# LoadCell-Board.net
KiCad netlist of a schematic drawn in EAGLE
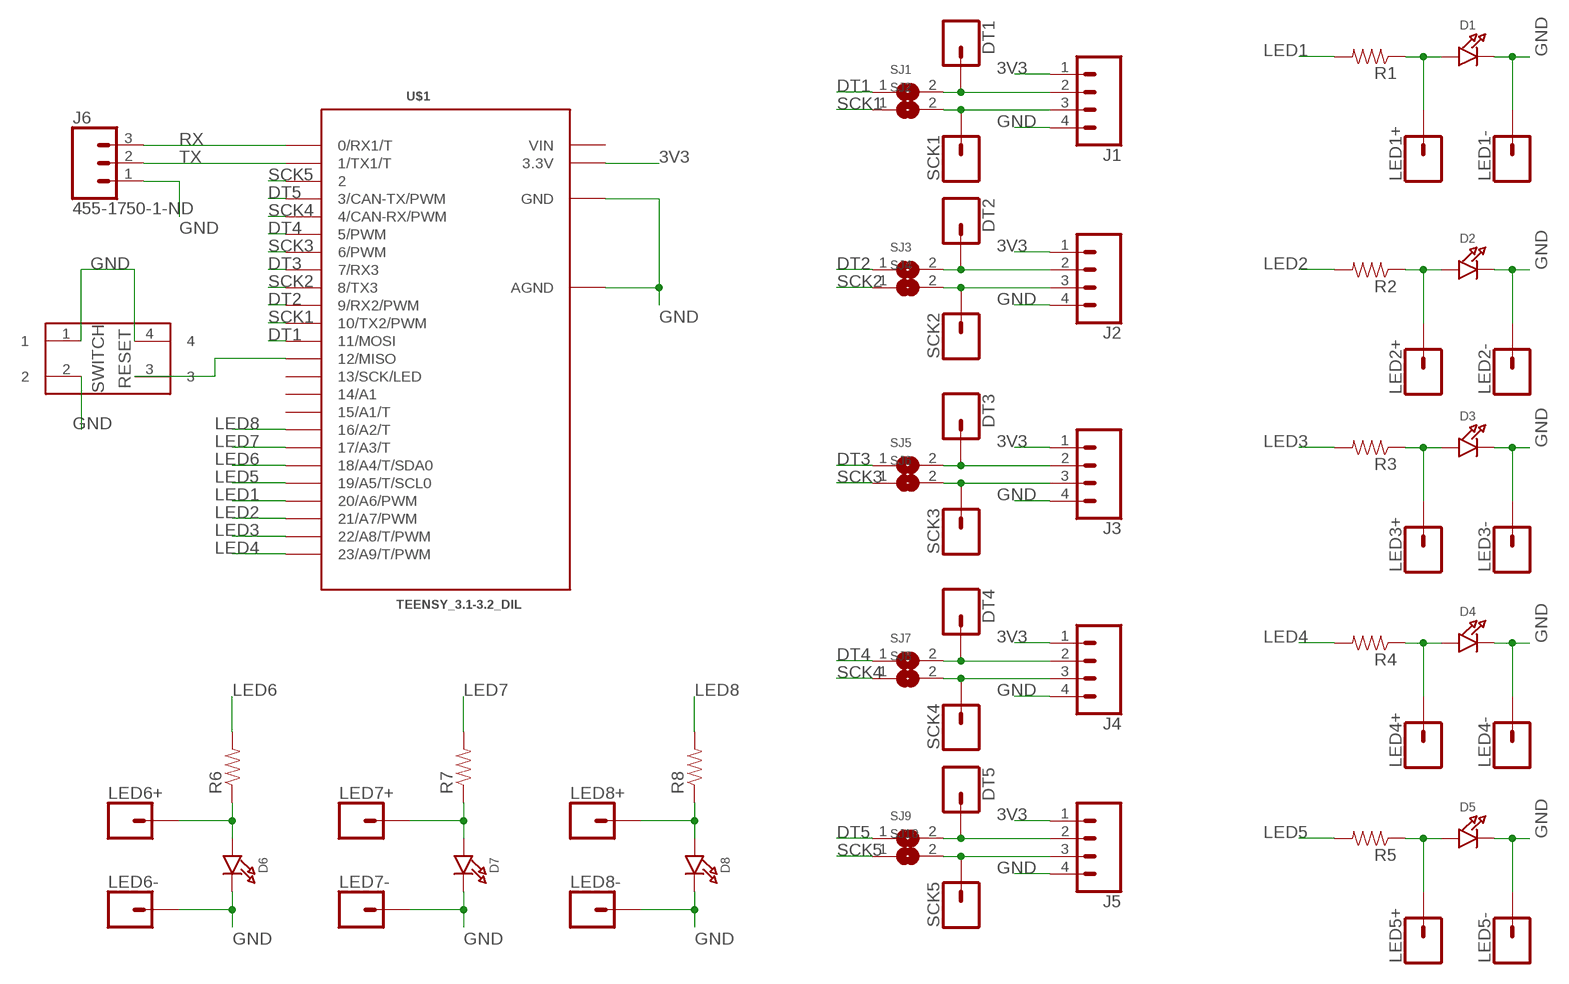
[diagram p0: schematic, sheet 1]

(export (version "E")
  (design (tool "Eeschema 10.0.6"))
  (components
    (comp (ref "D1")
      (value "MICROBUILDER_LED0603")
      (footprint "eagle-import:MICROBUILDER_CHIPLED_0603")
      (libsource (lib "eagle-import") (part "MICROBUILDER_LED0603"))
    )
    (comp (ref "D2")
      (value "MICROBUILDER_LED0603")
      (footprint "eagle-import:MICROBUILDER_CHIPLED_0603")
      (libsource (lib "eagle-import") (part "MICROBUILDER_LED0603"))
    )
    (comp (ref "D3")
      (value "MICROBUILDER_LED0603")
      (footprint "eagle-import:MICROBUILDER_CHIPLED_0603")
      (libsource (lib "eagle-import") (part "MICROBUILDER_LED0603"))
    )
    (comp (ref "D4")
      (value "MICROBUILDER_LED0603")
      (footprint "eagle-import:MICROBUILDER_CHIPLED_0603")
      (libsource (lib "eagle-import") (part "MICROBUILDER_LED0603"))
    )
    (comp (ref "D5")
      (value "MICROBUILDER_LED0603")
      (footprint "eagle-import:MICROBUILDER_CHIPLED_0603")
      (libsource (lib "eagle-import") (part "MICROBUILDER_LED0603"))
    )
    (comp (ref "D6")
      (value "MICROBUILDER_LED0603")
      (footprint "eagle-import:MICROBUILDER_CHIPLED_0603")
      (libsource (lib "eagle-import") (part "MICROBUILDER_LED0603"))
    )
    (comp (ref "D7")
      (value "MICROBUILDER_LED0603")
      (footprint "eagle-import:MICROBUILDER_CHIPLED_0603")
      (libsource (lib "eagle-import") (part "MICROBUILDER_LED0603"))
    )
    (comp (ref "D8")
      (value "MICROBUILDER_LED0603")
      (footprint "eagle-import:MICROBUILDER_CHIPLED_0603")
      (libsource (lib "eagle-import") (part "MICROBUILDER_LED0603"))
    )
    (comp (ref "DT1")
      (value "CONN_01")
      (footprint "eagle-import:1X01")
      (libsource (lib "eagle-import") (part "CONN_01"))
    )
    (comp (ref "DT2")
      (value "CONN_01")
      (footprint "eagle-import:1X01")
      (libsource (lib "eagle-import") (part "CONN_01"))
    )
    (comp (ref "DT3")
      (value "CONN_01")
      (footprint "eagle-import:1X01")
      (libsource (lib "eagle-import") (part "CONN_01"))
    )
    (comp (ref "DT4")
      (value "CONN_01")
      (footprint "eagle-import:1X01")
      (libsource (lib "eagle-import") (part "CONN_01"))
    )
    (comp (ref "DT5")
      (value "CONN_01")
      (footprint "eagle-import:1X01")
      (libsource (lib "eagle-import") (part "CONN_01"))
    )
    (comp (ref "J1")
      (value "CONN_041X04_NO_SILK")
      (footprint "eagle-import:1X04_NO_SILK")
      (libsource (lib "eagle-import") (part "CONN_041X04_NO_SILK"))
    )
    (comp (ref "J2")
      (value "CONN_041X04_NO_SILK")
      (footprint "eagle-import:1X04_NO_SILK")
      (libsource (lib "eagle-import") (part "CONN_041X04_NO_SILK"))
    )
    (comp (ref "J3")
      (value "CONN_041X04_NO_SILK")
      (footprint "eagle-import:1X04_NO_SILK")
      (libsource (lib "eagle-import") (part "CONN_041X04_NO_SILK"))
    )
    (comp (ref "J4")
      (value "CONN_041X04_NO_SILK")
      (footprint "eagle-import:1X04_NO_SILK")
      (libsource (lib "eagle-import") (part "CONN_041X04_NO_SILK"))
    )
    (comp (ref "J5")
      (value "CONN_041X04_NO_SILK")
      (footprint "eagle-import:1X04_NO_SILK")
      (libsource (lib "eagle-import") (part "CONN_041X04_NO_SILK"))
    )
    (comp (ref "J6")
      (value "455-1750-1-ND")
      (footprint "eagle-import:1X03")
      (libsource (lib "eagle-import") (part "CONN_03"))
    )
    (comp (ref "LED1+")
      (value "CONN_01PTH_NO_SILK_YES_STOP")
      (footprint "eagle-import:1X01_NO_SILK")
      (libsource (lib "eagle-import") (part "CONN_01PTH_NO_SILK_YES_STOP"))
    )
    (comp (ref "LED1-")
      (value "CONN_01PTH_NO_SILK_YES_STOP")
      (footprint "eagle-import:1X01_NO_SILK")
      (libsource (lib "eagle-import") (part "CONN_01PTH_NO_SILK_YES_STOP"))
    )
    (comp (ref "LED2+")
      (value "CONN_01PTH_NO_SILK_YES_STOP")
      (footprint "eagle-import:1X01_NO_SILK")
      (libsource (lib "eagle-import") (part "CONN_01PTH_NO_SILK_YES_STOP"))
    )
    (comp (ref "LED2-")
      (value "CONN_01PTH_NO_SILK_YES_STOP")
      (footprint "eagle-import:1X01_NO_SILK")
      (libsource (lib "eagle-import") (part "CONN_01PTH_NO_SILK_YES_STOP"))
    )
    (comp (ref "LED3+")
      (value "CONN_01PTH_NO_SILK_YES_STOP")
      (footprint "eagle-import:1X01_NO_SILK")
      (libsource (lib "eagle-import") (part "CONN_01PTH_NO_SILK_YES_STOP"))
    )
    (comp (ref "LED3-")
      (value "CONN_01PTH_NO_SILK_YES_STOP")
      (footprint "eagle-import:1X01_NO_SILK")
      (libsource (lib "eagle-import") (part "CONN_01PTH_NO_SILK_YES_STOP"))
    )
    (comp (ref "LED4+")
      (value "CONN_01PTH_NO_SILK_YES_STOP")
      (footprint "eagle-import:1X01_NO_SILK")
      (libsource (lib "eagle-import") (part "CONN_01PTH_NO_SILK_YES_STOP"))
    )
    (comp (ref "LED4-")
      (value "CONN_01PTH_NO_SILK_YES_STOP")
      (footprint "eagle-import:1X01_NO_SILK")
      (libsource (lib "eagle-import") (part "CONN_01PTH_NO_SILK_YES_STOP"))
    )
    (comp (ref "LED5+")
      (value "CONN_01PTH_NO_SILK_YES_STOP")
      (footprint "eagle-import:1X01_NO_SILK")
      (libsource (lib "eagle-import") (part "CONN_01PTH_NO_SILK_YES_STOP"))
    )
    (comp (ref "LED5-")
      (value "CONN_01PTH_NO_SILK_YES_STOP")
      (footprint "eagle-import:1X01_NO_SILK")
      (libsource (lib "eagle-import") (part "CONN_01PTH_NO_SILK_YES_STOP"))
    )
    (comp (ref "LED6+")
      (value "CONN_01PTH_NO_SILK_YES_STOP")
      (footprint "eagle-import:1X01_NO_SILK")
      (libsource (lib "eagle-import") (part "CONN_01PTH_NO_SILK_YES_STOP"))
    )
    (comp (ref "LED6-")
      (value "CONN_01PTH_NO_SILK_YES_STOP")
      (footprint "eagle-import:1X01_NO_SILK")
      (libsource (lib "eagle-import") (part "CONN_01PTH_NO_SILK_YES_STOP"))
    )
    (comp (ref "LED7+")
      (value "CONN_01PTH_NO_SILK_YES_STOP")
      (footprint "eagle-import:1X01_NO_SILK")
      (libsource (lib "eagle-import") (part "CONN_01PTH_NO_SILK_YES_STOP"))
    )
    (comp (ref "LED7-")
      (value "CONN_01PTH_NO_SILK_YES_STOP")
      (footprint "eagle-import:1X01_NO_SILK")
      (libsource (lib "eagle-import") (part "CONN_01PTH_NO_SILK_YES_STOP"))
    )
    (comp (ref "LED8+")
      (value "CONN_01PTH_NO_SILK_YES_STOP")
      (footprint "eagle-import:1X01_NO_SILK")
      (libsource (lib "eagle-import") (part "CONN_01PTH_NO_SILK_YES_STOP"))
    )
    (comp (ref "LED8-")
      (value "CONN_01PTH_NO_SILK_YES_STOP")
      (footprint "eagle-import:1X01_NO_SILK")
      (libsource (lib "eagle-import") (part "CONN_01PTH_NO_SILK_YES_STOP"))
    )
    (comp (ref "R1")
      (value "CONTROLBOARD_V1.0_SPARKFUN_RESISTOR0603-RES")
      (footprint "eagle-import:CONTROLBOARD_V1.0_SPARKFUN_0603-RES")
      (libsource (lib "eagle-import") (part "CONTROLBOARD_V1.0_SPARKFUN_RESISTOR0603-RES"))
    )
    (comp (ref "R2")
      (value "CONTROLBOARD_V1.0_SPARKFUN_RESISTOR0603-RES")
      (footprint "eagle-import:CONTROLBOARD_V1.0_SPARKFUN_0603-RES")
      (libsource (lib "eagle-import") (part "CONTROLBOARD_V1.0_SPARKFUN_RESISTOR0603-RES"))
    )
    (comp (ref "R3")
      (value "CONTROLBOARD_V1.0_SPARKFUN_RESISTOR0603-RES")
      (footprint "eagle-import:CONTROLBOARD_V1.0_SPARKFUN_0603-RES")
      (libsource (lib "eagle-import") (part "CONTROLBOARD_V1.0_SPARKFUN_RESISTOR0603-RES"))
    )
    (comp (ref "R4")
      (value "CONTROLBOARD_V1.0_SPARKFUN_RESISTOR0603-RES")
      (footprint "eagle-import:CONTROLBOARD_V1.0_SPARKFUN_0603-RES")
      (libsource (lib "eagle-import") (part "CONTROLBOARD_V1.0_SPARKFUN_RESISTOR0603-RES"))
    )
    (comp (ref "R5")
      (value "CONTROLBOARD_V1.0_SPARKFUN_RESISTOR0603-RES")
      (footprint "eagle-import:CONTROLBOARD_V1.0_SPARKFUN_0603-RES")
      (libsource (lib "eagle-import") (part "CONTROLBOARD_V1.0_SPARKFUN_RESISTOR0603-RES"))
    )
    (comp (ref "R6")
      (value "CONTROLBOARD_V1.0_SPARKFUN_RESISTOR0603-RES")
      (footprint "eagle-import:CONTROLBOARD_V1.0_SPARKFUN_0603-RES")
      (libsource (lib "eagle-import") (part "CONTROLBOARD_V1.0_SPARKFUN_RESISTOR0603-RES"))
    )
    (comp (ref "R7")
      (value "CONTROLBOARD_V1.0_SPARKFUN_RESISTOR0603-RES")
      (footprint "eagle-import:CONTROLBOARD_V1.0_SPARKFUN_0603-RES")
      (libsource (lib "eagle-import") (part "CONTROLBOARD_V1.0_SPARKFUN_RESISTOR0603-RES"))
    )
    (comp (ref "R8")
      (value "CONTROLBOARD_V1.0_SPARKFUN_RESISTOR0603-RES")
      (footprint "eagle-import:CONTROLBOARD_V1.0_SPARKFUN_0603-RES")
      (libsource (lib "eagle-import") (part "CONTROLBOARD_V1.0_SPARKFUN_RESISTOR0603-RES"))
    )
    (comp (ref "RESET")
      (value "SWITCH")
      (footprint "eagle-import:431256038716")
      (libsource (lib "eagle-import") (part "431256038716"))
    )
    (comp (ref "SCK1")
      (value "CONN_01")
      (footprint "eagle-import:1X01")
      (libsource (lib "eagle-import") (part "CONN_01"))
    )
    (comp (ref "SCK2")
      (value "CONN_01")
      (footprint "eagle-import:1X01")
      (libsource (lib "eagle-import") (part "CONN_01"))
    )
    (comp (ref "SCK3")
      (value "CONN_01")
      (footprint "eagle-import:1X01")
      (libsource (lib "eagle-import") (part "CONN_01"))
    )
    (comp (ref "SCK4")
      (value "CONN_01")
      (footprint "eagle-import:1X01")
      (libsource (lib "eagle-import") (part "CONN_01"))
    )
    (comp (ref "SCK5")
      (value "CONN_01")
      (footprint "eagle-import:1X01")
      (libsource (lib "eagle-import") (part "CONN_01"))
    )
    (comp (ref "SJ1")
      (value "MICROBUILDER_SOLDERJUMPERREFLOW_NOPASTE")
      (footprint "eagle-import:MICROBUILDER_SOLDERJUMPER_REFLOW_NOPASTE")
      (libsource (lib "eagle-import") (part "MICROBUILDER_SOLDERJUMPERREFLOW_NOPASTE"))
    )
    (comp (ref "SJ2")
      (value "MICROBUILDER_SOLDERJUMPERREFLOW_NOPASTE")
      (footprint "eagle-import:MICROBUILDER_SOLDERJUMPER_REFLOW_NOPASTE")
      (libsource (lib "eagle-import") (part "MICROBUILDER_SOLDERJUMPERREFLOW_NOPASTE"))
    )
    (comp (ref "SJ3")
      (value "MICROBUILDER_SOLDERJUMPERREFLOW_NOPASTE")
      (footprint "eagle-import:MICROBUILDER_SOLDERJUMPER_REFLOW_NOPASTE")
      (libsource (lib "eagle-import") (part "MICROBUILDER_SOLDERJUMPERREFLOW_NOPASTE"))
    )
    (comp (ref "SJ4")
      (value "MICROBUILDER_SOLDERJUMPERREFLOW_NOPASTE")
      (footprint "eagle-import:MICROBUILDER_SOLDERJUMPER_REFLOW_NOPASTE")
      (libsource (lib "eagle-import") (part "MICROBUILDER_SOLDERJUMPERREFLOW_NOPASTE"))
    )
    (comp (ref "SJ5")
      (value "MICROBUILDER_SOLDERJUMPERREFLOW_NOPASTE")
      (footprint "eagle-import:MICROBUILDER_SOLDERJUMPER_REFLOW_NOPASTE")
      (libsource (lib "eagle-import") (part "MICROBUILDER_SOLDERJUMPERREFLOW_NOPASTE"))
    )
    (comp (ref "SJ6")
      (value "MICROBUILDER_SOLDERJUMPERREFLOW_NOPASTE")
      (footprint "eagle-import:MICROBUILDER_SOLDERJUMPER_REFLOW_NOPASTE")
      (libsource (lib "eagle-import") (part "MICROBUILDER_SOLDERJUMPERREFLOW_NOPASTE"))
    )
    (comp (ref "SJ7")
      (value "MICROBUILDER_SOLDERJUMPERREFLOW_NOPASTE")
      (footprint "eagle-import:MICROBUILDER_SOLDERJUMPER_REFLOW_NOPASTE")
      (libsource (lib "eagle-import") (part "MICROBUILDER_SOLDERJUMPERREFLOW_NOPASTE"))
    )
    (comp (ref "SJ8")
      (value "MICROBUILDER_SOLDERJUMPERREFLOW_NOPASTE")
      (footprint "eagle-import:MICROBUILDER_SOLDERJUMPER_REFLOW_NOPASTE")
      (libsource (lib "eagle-import") (part "MICROBUILDER_SOLDERJUMPERREFLOW_NOPASTE"))
    )
    (comp (ref "SJ9")
      (value "MICROBUILDER_SOLDERJUMPERREFLOW_NOPASTE")
      (footprint "eagle-import:MICROBUILDER_SOLDERJUMPER_REFLOW_NOPASTE")
      (libsource (lib "eagle-import") (part "MICROBUILDER_SOLDERJUMPERREFLOW_NOPASTE"))
    )
    (comp (ref "SJ10")
      (value "MICROBUILDER_SOLDERJUMPERREFLOW_NOPASTE")
      (footprint "eagle-import:MICROBUILDER_SOLDERJUMPER_REFLOW_NOPASTE")
      (libsource (lib "eagle-import") (part "MICROBUILDER_SOLDERJUMPERREFLOW_NOPASTE"))
    )
    (comp (ref "U$1")
      (value "TEENSY_3.1-3.2_DIL")
      (footprint "eagle-import:TEENSY_3.0-3.2&LC_DIL")
      (libsource (lib "eagle-import") (part "TEENSY_3.1-3.2_DIL"))
    )
  )
  (nets
    (net (code "1") (name "/3V3") (class "Default")
      (node (ref "J1") (pin "1") (pinfunction "1_1") (pintype "passive"))
      (node (ref "J2") (pin "1") (pinfunction "1_1") (pintype "passive"))
      (node (ref "J3") (pin "1") (pinfunction "1_1") (pintype "passive"))
      (node (ref "J4") (pin "1") (pinfunction "1_1") (pintype "passive"))
      (node (ref "J5") (pin "1") (pinfunction "1_1") (pintype "passive"))
      (node (ref "U$1") (pin "3.3V") (pinfunction "3.3V_3.3V") (pintype "power_in"))
    )
    (net (code "2") (name "/DT1") (class "Default")
      (node (ref "SJ1") (pin "1") (pinfunction "1_1") (pintype "passive"))
      (node (ref "U$1") (pin "11") (pinfunction "11/MOSI_11") (pintype "bidirectional"))
    )
    (net (code "3") (name "/DT2") (class "Default")
      (node (ref "SJ3") (pin "1") (pinfunction "1_1") (pintype "passive"))
      (node (ref "U$1") (pin "9") (pinfunction "9/RX2/PWM_9") (pintype "bidirectional"))
    )
    (net (code "4") (name "/DT3") (class "Default")
      (node (ref "SJ5") (pin "1") (pinfunction "1_1") (pintype "passive"))
      (node (ref "U$1") (pin "7") (pinfunction "7/RX3_7") (pintype "bidirectional"))
    )
    (net (code "5") (name "/DT4") (class "Default")
      (node (ref "SJ7") (pin "1") (pinfunction "1_1") (pintype "passive"))
      (node (ref "U$1") (pin "5") (pinfunction "5/PWM_5") (pintype "bidirectional"))
    )
    (net (code "6") (name "/DT5") (class "Default")
      (node (ref "SJ9") (pin "1") (pinfunction "1_1") (pintype "passive"))
      (node (ref "U$1") (pin "3") (pinfunction "3/CAN-TX/PWM_3") (pintype "bidirectional"))
    )
    (net (code "7") (name "/GND") (class "Default")
      (node (ref "D1") (pin "C") (pinfunction "C_C") (pintype "passive"))
      (node (ref "D2") (pin "C") (pinfunction "C_C") (pintype "passive"))
      (node (ref "D3") (pin "C") (pinfunction "C_C") (pintype "passive"))
      (node (ref "D4") (pin "C") (pinfunction "C_C") (pintype "passive"))
      (node (ref "D5") (pin "C") (pinfunction "C_C") (pintype "passive"))
      (node (ref "D6") (pin "C") (pinfunction "C_C") (pintype "passive"))
      (node (ref "D7") (pin "C") (pinfunction "C_C") (pintype "passive"))
      (node (ref "D8") (pin "C") (pinfunction "C_C") (pintype "passive"))
      (node (ref "J1") (pin "4") (pinfunction "4_4") (pintype "passive"))
      (node (ref "J2") (pin "4") (pinfunction "4_4") (pintype "passive"))
      (node (ref "J3") (pin "4") (pinfunction "4_4") (pintype "passive"))
      (node (ref "J4") (pin "4") (pinfunction "4_4") (pintype "passive"))
      (node (ref "J5") (pin "4") (pinfunction "4_4") (pintype "passive"))
      (node (ref "J6") (pin "1") (pinfunction "1_1") (pintype "passive"))
      (node (ref "LED1-") (pin "1") (pinfunction "1_1") (pintype "passive"))
      (node (ref "LED2-") (pin "1") (pinfunction "1_1") (pintype "passive"))
      (node (ref "LED3-") (pin "1") (pinfunction "1_1") (pintype "passive"))
      (node (ref "LED4-") (pin "1") (pinfunction "1_1") (pintype "passive"))
      (node (ref "LED5-") (pin "1") (pinfunction "1_1") (pintype "passive"))
      (node (ref "LED6-") (pin "1") (pinfunction "1_1") (pintype "passive"))
      (node (ref "LED7-") (pin "1") (pinfunction "1_1") (pintype "passive"))
      (node (ref "LED8-") (pin "1") (pinfunction "1_1") (pintype "passive"))
      (node (ref "RESET") (pin "1") (pinfunction "1_1") (pintype "bidirectional"))
      (node (ref "RESET") (pin "2") (pinfunction "2_2") (pintype "bidirectional"))
      (node (ref "RESET") (pin "4") (pinfunction "4_4") (pintype "bidirectional"))
      (node (ref "U$1") (pin "AGND") (pinfunction "AGND_AGND") (pintype "power_in"))
      (node (ref "U$1") (pin "GND") (pinfunction "GND_GND") (pintype "power_in"))
    )
    (net (code "8") (name "/LED1") (class "Default")
      (node (ref "R1") (pin "2") (pinfunction "2_2") (pintype "passive"))
      (node (ref "U$1") (pin "20/A6") (pinfunction "20/A6/PWM_20/A6") (pintype "bidirectional"))
    )
    (net (code "9") (name "/LED2") (class "Default")
      (node (ref "R2") (pin "2") (pinfunction "2_2") (pintype "passive"))
      (node (ref "U$1") (pin "21/A7") (pinfunction "21/A7/PWM_21/A7") (pintype "bidirectional"))
    )
    (net (code "10") (name "/LED3") (class "Default")
      (node (ref "R3") (pin "2") (pinfunction "2_2") (pintype "passive"))
      (node (ref "U$1") (pin "22/A8") (pinfunction "22/A8/T/PWM_22/A8") (pintype "bidirectional"))
    )
    (net (code "11") (name "/LED4") (class "Default")
      (node (ref "R4") (pin "2") (pinfunction "2_2") (pintype "passive"))
      (node (ref "U$1") (pin "23/A9") (pinfunction "23/A9/T/PWM_23/A9") (pintype "bidirectional"))
    )
    (net (code "12") (name "/LED5") (class "Default")
      (node (ref "R5") (pin "2") (pinfunction "2_2") (pintype "passive"))
      (node (ref "U$1") (pin "19/A5") (pinfunction "19/A5/T/SCL0_19/A5") (pintype "bidirectional"))
    )
    (net (code "13") (name "/LED6") (class "Default")
      (node (ref "R6") (pin "2") (pinfunction "2_2") (pintype "passive"))
      (node (ref "U$1") (pin "18/A4") (pinfunction "18/A4/T/SDA0_18/A4") (pintype "bidirectional"))
    )
    (net (code "14") (name "/LED7") (class "Default")
      (node (ref "R7") (pin "2") (pinfunction "2_2") (pintype "passive"))
      (node (ref "U$1") (pin "17/A3") (pinfunction "17/A3/T_17/A3") (pintype "bidirectional"))
    )
    (net (code "15") (name "/LED8") (class "Default")
      (node (ref "R8") (pin "2") (pinfunction "2_2") (pintype "passive"))
      (node (ref "U$1") (pin "16/A2") (pinfunction "16/A2/T_16/A2") (pintype "bidirectional"))
    )
    (net (code "16") (name "/RX") (class "Default")
      (node (ref "J6") (pin "3") (pinfunction "3_3") (pintype "passive"))
      (node (ref "U$1") (pin "0") (pinfunction "0/RX1/T_0") (pintype "bidirectional"))
    )
    (net (code "17") (name "/SCK1") (class "Default")
      (node (ref "SJ2") (pin "1") (pinfunction "1_1") (pintype "passive"))
      (node (ref "U$1") (pin "10") (pinfunction "10/TX2/PWM_10") (pintype "bidirectional"))
    )
    (net (code "18") (name "/SCK2") (class "Default")
      (node (ref "SJ4") (pin "1") (pinfunction "1_1") (pintype "passive"))
      (node (ref "U$1") (pin "8") (pinfunction "8/TX3_8") (pintype "bidirectional"))
    )
    (net (code "19") (name "/SCK3") (class "Default")
      (node (ref "SJ6") (pin "1") (pinfunction "1_1") (pintype "passive"))
      (node (ref "U$1") (pin "6") (pinfunction "6/PWM_6") (pintype "bidirectional"))
    )
    (net (code "20") (name "/SCK4") (class "Default")
      (node (ref "SJ8") (pin "1") (pinfunction "1_1") (pintype "passive"))
      (node (ref "U$1") (pin "4") (pinfunction "4/CAN-RX/PWM_4") (pintype "bidirectional"))
    )
    (net (code "21") (name "/SCK5") (class "Default")
      (node (ref "SJ10") (pin "1") (pinfunction "1_1") (pintype "passive"))
      (node (ref "U$1") (pin "2") (pinfunction "2_2") (pintype "bidirectional"))
    )
    (net (code "22") (name "/TX") (class "Default")
      (node (ref "J6") (pin "2") (pinfunction "2_2") (pintype "passive"))
      (node (ref "U$1") (pin "1") (pinfunction "1/TX1/T_1") (pintype "bidirectional"))
    )
    (net (code "23") (name "/VIN") (class "Default")
      (node (ref "U$1") (pin "VIN") (pinfunction "VIN_VIN") (pintype "power_in"))
    )
    (net (code "24") (name "Net-(D1-PadA)") (class "Default")
      (node (ref "D1") (pin "A") (pinfunction "A_A") (pintype "passive"))
      (node (ref "LED1+") (pin "1") (pinfunction "1_1") (pintype "passive"))
      (node (ref "R1") (pin "1") (pinfunction "1_1") (pintype "passive"))
    )
    (net (code "25") (name "Net-(D2-PadA)") (class "Default")
      (node (ref "D2") (pin "A") (pinfunction "A_A") (pintype "passive"))
      (node (ref "LED2+") (pin "1") (pinfunction "1_1") (pintype "passive"))
      (node (ref "R2") (pin "1") (pinfunction "1_1") (pintype "passive"))
    )
    (net (code "26") (name "Net-(D3-PadA)") (class "Default")
      (node (ref "D3") (pin "A") (pinfunction "A_A") (pintype "passive"))
      (node (ref "LED3+") (pin "1") (pinfunction "1_1") (pintype "passive"))
      (node (ref "R3") (pin "1") (pinfunction "1_1") (pintype "passive"))
    )
    (net (code "27") (name "Net-(D4-PadA)") (class "Default")
      (node (ref "D4") (pin "A") (pinfunction "A_A") (pintype "passive"))
      (node (ref "LED4+") (pin "1") (pinfunction "1_1") (pintype "passive"))
      (node (ref "R4") (pin "1") (pinfunction "1_1") (pintype "passive"))
    )
    (net (code "28") (name "Net-(D5-PadA)") (class "Default")
      (node (ref "D5") (pin "A") (pinfunction "A_A") (pintype "passive"))
      (node (ref "LED5+") (pin "1") (pinfunction "1_1") (pintype "passive"))
      (node (ref "R5") (pin "1") (pinfunction "1_1") (pintype "passive"))
    )
    (net (code "29") (name "Net-(D6-PadA)") (class "Default")
      (node (ref "D6") (pin "A") (pinfunction "A_A") (pintype "passive"))
      (node (ref "LED6+") (pin "1") (pinfunction "1_1") (pintype "passive"))
      (node (ref "R6") (pin "1") (pinfunction "1_1") (pintype "passive"))
    )
    (net (code "30") (name "Net-(D7-PadA)") (class "Default")
      (node (ref "D7") (pin "A") (pinfunction "A_A") (pintype "passive"))
      (node (ref "LED7+") (pin "1") (pinfunction "1_1") (pintype "passive"))
      (node (ref "R7") (pin "1") (pinfunction "1_1") (pintype "passive"))
    )
    (net (code "31") (name "Net-(D8-PadA)") (class "Default")
      (node (ref "D8") (pin "A") (pinfunction "A_A") (pintype "passive"))
      (node (ref "LED8+") (pin "1") (pinfunction "1_1") (pintype "passive"))
      (node (ref "R8") (pin "1") (pinfunction "1_1") (pintype "passive"))
    )
    (net (code "32") (name "Net-(DT1-Pad1)") (class "Default")
      (node (ref "DT1") (pin "1") (pinfunction "1_1") (pintype "passive"))
      (node (ref "J1") (pin "2") (pinfunction "2_2") (pintype "passive"))
      (node (ref "SJ1") (pin "2") (pinfunction "2_2") (pintype "passive"))
    )
    (net (code "33") (name "Net-(DT2-Pad1)") (class "Default")
      (node (ref "DT2") (pin "1") (pinfunction "1_1") (pintype "passive"))
      (node (ref "J2") (pin "2") (pinfunction "2_2") (pintype "passive"))
      (node (ref "SJ3") (pin "2") (pinfunction "2_2") (pintype "passive"))
    )
    (net (code "34") (name "Net-(DT3-Pad1)") (class "Default")
      (node (ref "DT3") (pin "1") (pinfunction "1_1") (pintype "passive"))
      (node (ref "J3") (pin "2") (pinfunction "2_2") (pintype "passive"))
      (node (ref "SJ5") (pin "2") (pinfunction "2_2") (pintype "passive"))
    )
    (net (code "35") (name "Net-(DT4-Pad1)") (class "Default")
      (node (ref "DT4") (pin "1") (pinfunction "1_1") (pintype "passive"))
      (node (ref "J4") (pin "2") (pinfunction "2_2") (pintype "passive"))
      (node (ref "SJ7") (pin "2") (pinfunction "2_2") (pintype "passive"))
    )
    (net (code "36") (name "Net-(DT5-Pad1)") (class "Default")
      (node (ref "DT5") (pin "1") (pinfunction "1_1") (pintype "passive"))
      (node (ref "J5") (pin "2") (pinfunction "2_2") (pintype "passive"))
      (node (ref "SJ9") (pin "2") (pinfunction "2_2") (pintype "passive"))
    )
    (net (code "37") (name "Net-(J1-Pad3)") (class "Default")
      (node (ref "J1") (pin "3") (pinfunction "3_3") (pintype "passive"))
      (node (ref "SCK1") (pin "1") (pinfunction "1_1") (pintype "passive"))
      (node (ref "SJ2") (pin "2") (pinfunction "2_2") (pintype "passive"))
    )
    (net (code "38") (name "Net-(J2-Pad3)") (class "Default")
      (node (ref "J2") (pin "3") (pinfunction "3_3") (pintype "passive"))
      (node (ref "SCK2") (pin "1") (pinfunction "1_1") (pintype "passive"))
      (node (ref "SJ4") (pin "2") (pinfunction "2_2") (pintype "passive"))
    )
    (net (code "39") (name "Net-(J3-Pad3)") (class "Default")
      (node (ref "J3") (pin "3") (pinfunction "3_3") (pintype "passive"))
      (node (ref "SCK3") (pin "1") (pinfunction "1_1") (pintype "passive"))
      (node (ref "SJ6") (pin "2") (pinfunction "2_2") (pintype "passive"))
    )
    (net (code "40") (name "Net-(J4-Pad3)") (class "Default")
      (node (ref "J4") (pin "3") (pinfunction "3_3") (pintype "passive"))
      (node (ref "SCK4") (pin "1") (pinfunction "1_1") (pintype "passive"))
      (node (ref "SJ8") (pin "2") (pinfunction "2_2") (pintype "passive"))
    )
    (net (code "41") (name "Net-(J5-Pad3)") (class "Default")
      (node (ref "J5") (pin "3") (pinfunction "3_3") (pintype "passive"))
      (node (ref "SCK5") (pin "1") (pinfunction "1_1") (pintype "passive"))
      (node (ref "SJ10") (pin "2") (pinfunction "2_2") (pintype "passive"))
    )
    (net (code "42") (name "Net-(U$1-12{slash}MISO)") (class "Default")
      (node (ref "RESET") (pin "3") (pinfunction "3_3") (pintype "bidirectional"))
      (node (ref "U$1") (pin "12") (pinfunction "12/MISO_12") (pintype "bidirectional"))
    )
    (net (code "43") (name "unconnected-(U$1-13{slash}SCK{slash}LED-Pad13)") (class "Default")
      (node (ref "U$1") (pin "13") (pinfunction "13/SCK/LED_13") (pintype "bidirectional"))
    )
    (net (code "44") (name "unconnected-(U$1-14{slash}A1-Pad14{slash}A0)") (class "Default")
      (node (ref "U$1") (pin "14/A0") (pinfunction "14/A1_14/A0") (pintype "bidirectional"))
    )
    (net (code "45") (name "unconnected-(U$1-15{slash}A1{slash}T-Pad15{slash}A1)") (class "Default")
      (node (ref "U$1") (pin "15/A1") (pinfunction "15/A1/T_15/A1") (pintype "bidirectional"))
    )
  )
)
